# Distortion_outputbuffer.net
KiCad netlist of a schematic drawn in Altium Designer
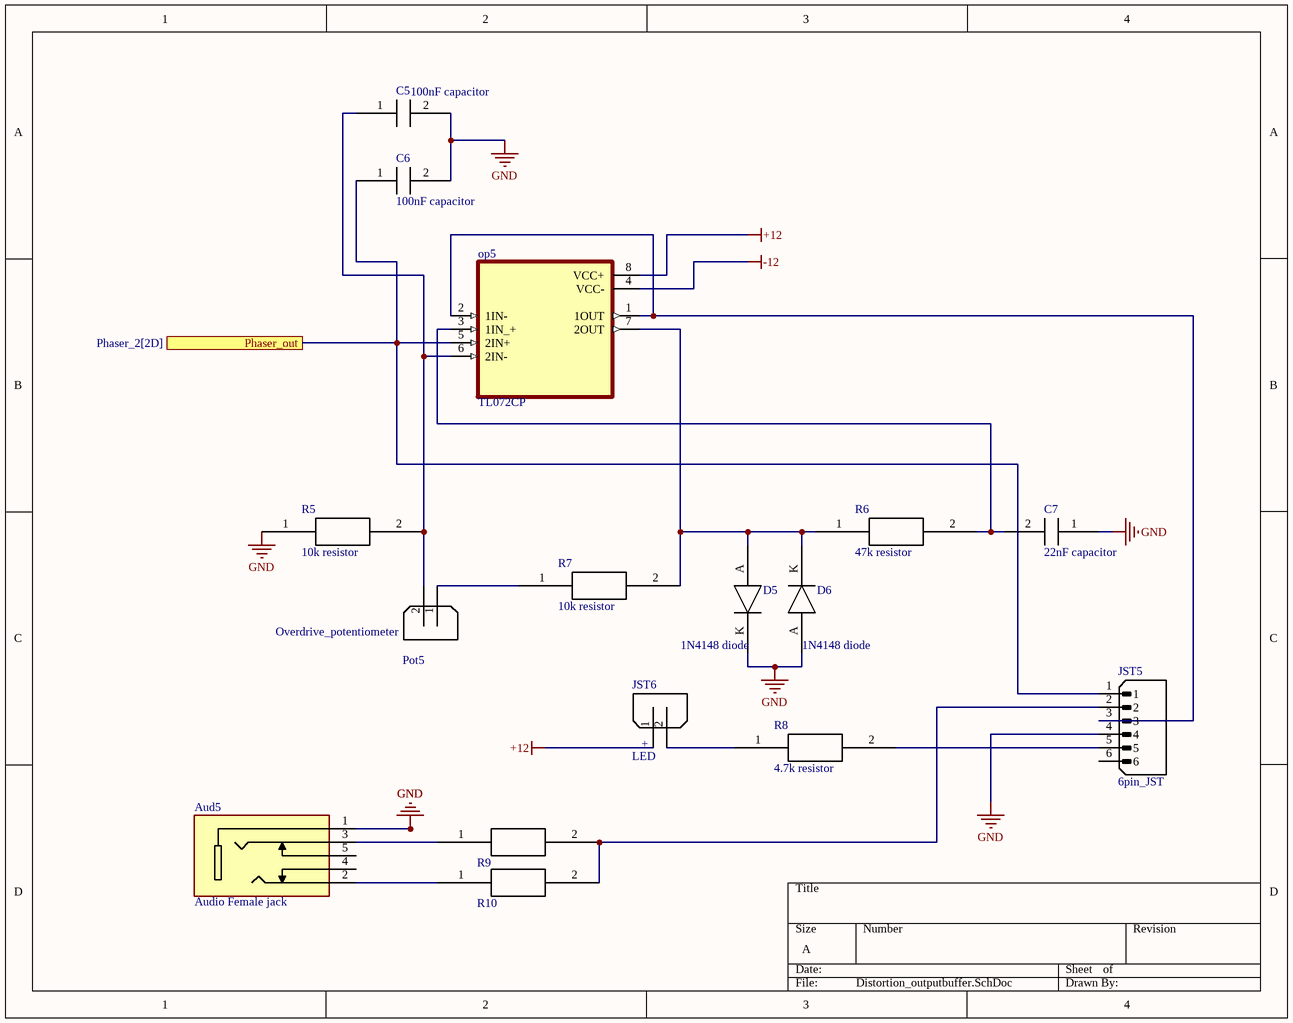
[diagram p0: Distortion_outputbuffer.SchDoc]

(export (version "E")
  (design (tool "Eeschema 10.0.6"))
  (components
    (comp (ref "Aud5")
      (value "Audio Female jack")
      (footprint "Audio Female Jack")
      (libsource (lib "Analog_Project_Schlib") (part "Audio Female jack"))
    )
    (comp (ref "C5")
      (value "100nF capacitor")
      (footprint "100nF")
      (libsource (lib "Analog_Project_Schlib") (part "100nF capacitor"))
    )
    (comp (ref "C6")
      (value "100nF capacitor")
      (footprint "100nF")
      (libsource (lib "Analog_Project_Schlib") (part "100nF capacitor"))
    )
    (comp (ref "C7")
      (value "22nF capacitor")
      (footprint "22nF")
      (libsource (lib "Analog_Project_Schlib") (part "22nF capacitor"))
    )
    (comp (ref "D5")
      (value "1N4148 diode")
      (footprint "1N4148")
      (libsource (lib "Analog_Project_Schlib") (part "1N4148 diode"))
    )
    (comp (ref "D6")
      (value "1N4148 diode")
      (footprint "1N4148")
      (libsource (lib "Analog_Project_Schlib") (part "1N4148 diode"))
    )
    (comp (ref "JST5")
      (value "6pin_JST")
      (footprint "6pin_JST")
      (libsource (lib "Analog_Project_Schlib") (part "6pin_JST"))
    )
    (comp (ref "JST6")
      (value "LED")
      (footprint "2pin_JST")
      (libsource (lib "Analog_Project_Schlib") (part "2pin_JST"))
    )
    (comp (ref "op5")
      (value "TL072CP")
      (footprint "TL072CP")
      (libsource (lib "Analog_Project_Schlib") (part "TL072CP"))
    )
    (comp (ref "Pot5")
      (value "Overdrive_potentiometer")
      (footprint "2pin_JST_non_polarized")
      (libsource (lib "Analog_Project_Schlib") (part "2pin_jst_non_polarized"))
    )
    (comp (ref "R5")
      (value "10k resistor")
      (footprint "10k")
      (libsource (lib "Analog_Project_Schlib") (part "10k resistor"))
    )
    (comp (ref "R6")
      (value "47k resistor")
      (footprint "47k")
      (libsource (lib "Analog_Project_Schlib") (part "47k resistor"))
    )
    (comp (ref "R7")
      (value "10k resistor")
      (footprint "10k")
      (libsource (lib "Analog_Project_Schlib") (part "10k resistor"))
    )
    (comp (ref "R8")
      (value "4.7k resistor")
      (footprint "4.7k")
      (libsource (lib "Analog_Project_Schlib") (part "4.7k resistor"))
    )
    (comp (ref "R9")
      (value "100ohm resistor")
      (footprint "100")
      (libsource (lib "Analog_Project_Schlib") (part "100ohm resistor"))
    )
    (comp (ref "R10")
      (value "100ohm resistor")
      (footprint "100")
      (libsource (lib "Analog_Project_Schlib") (part "100ohm resistor"))
    )
  )
  (nets
    (net (code "1") (name "+12") (class "Default")
      (node (ref "JST6") (pin "1") (pinfunction "1_1") (pintype "passive"))
      (node (ref "op5") (pin "8") (pinfunction "VCC+_8") (pintype "power_in"))
    )
    (net (code "2") (name "-12") (class "Default")
      (node (ref "op5") (pin "4") (pinfunction "VCC-_4") (pintype "power_in"))
    )
    (net (code "3") (name "/Phaser_out") (class "Default")
      (node (ref "C6") (pin "1") (pinfunction "1_1") (pintype "passive"))
      (node (ref "JST5") (pin "1") (pinfunction "1_1") (pintype "passive"))
      (node (ref "op5") (pin "5") (pinfunction "2IN+_5") (pintype "input"))
    )
    (net (code "4") (name "GND") (class "Default")
      (node (ref "Aud5") (pin "1") (pinfunction "1_1") (pintype "passive"))
      (node (ref "C5") (pin "2") (pintype "passive"))
      (node (ref "C6") (pin "2") (pintype "passive"))
      (node (ref "C7") (pin "1") (pinfunction "1_1") (pintype "passive"))
      (node (ref "D5") (pin "K") (pinfunction "K_K") (pintype "passive"))
      (node (ref "D6") (pin "A") (pinfunction "A_A") (pintype "passive"))
      (node (ref "JST5") (pin "4") (pinfunction "4_4") (pintype "passive"))
      (node (ref "R5") (pin "1") (pinfunction "1_1") (pintype "passive"))
    )
    (net (code "5") (name "Net-(Aud5-Pad2)") (class "Default")
      (node (ref "Aud5") (pin "2") (pinfunction "2_2") (pintype "passive"))
      (node (ref "R10") (pin "1") (pinfunction "1_1") (pintype "passive"))
    )
    (net (code "6") (name "Net-(Aud5-Pad3)") (class "Default")
      (node (ref "Aud5") (pin "3") (pinfunction "3_3") (pintype "passive"))
      (node (ref "R9") (pin "1") (pinfunction "1_1") (pintype "passive"))
    )
    (net (code "7") (name "Net-(C7-_2)") (class "Default")
      (node (ref "C7") (pin "2") (pinfunction "_2_2") (pintype "passive"))
      (node (ref "R6") (pin "2") (pinfunction "2_2") (pintype "passive"))
      (node (ref "op5") (pin "3") (pinfunction "1IN_+_3") (pintype "input"))
    )
    (net (code "8") (name "Net-(JST5-Pad2)") (class "Default")
      (node (ref "JST5") (pin "2") (pinfunction "2_2") (pintype "passive"))
      (node (ref "R10") (pin "2") (pinfunction "2_2") (pintype "passive"))
      (node (ref "R9") (pin "2") (pinfunction "2_2") (pintype "passive"))
    )
    (net (code "9") (name "Net-(JST5-Pad5)") (class "Default")
      (node (ref "JST5") (pin "5") (pinfunction "5_5") (pintype "passive"))
      (node (ref "R8") (pin "2") (pinfunction "2_2") (pintype "passive"))
    )
    (net (code "10") (name "Net-(JST6-Pad2)") (class "Default")
      (node (ref "JST6") (pin "2") (pinfunction "2_2") (pintype "passive"))
      (node (ref "R8") (pin "1") (pinfunction "1_1") (pintype "passive"))
    )
    (net (code "11") (name "Net-(Pot5-Pad1)") (class "Default")
      (node (ref "Pot5") (pin "1") (pinfunction "1_1") (pintype "passive"))
      (node (ref "R7") (pin "1") (pinfunction "1_1") (pintype "passive"))
    )
    (net (code "12") (name "Net-(op5-1IN-)") (class "Default")
      (node (ref "JST5") (pin "3") (pinfunction "3_3") (pintype "passive"))
      (node (ref "op5") (pin "1") (pinfunction "1OUT_1") (pintype "output"))
      (node (ref "op5") (pin "2") (pinfunction "1IN-_2") (pintype "input"))
    )
    (net (code "13") (name "Net-(op5-2IN-)") (class "Default")
      (node (ref "C5") (pin "1") (pinfunction "1_1") (pintype "passive"))
      (node (ref "Pot5") (pin "2") (pinfunction "2_2") (pintype "passive"))
      (node (ref "R5") (pin "2") (pinfunction "2_2") (pintype "passive"))
      (node (ref "op5") (pin "6") (pinfunction "2IN-_6") (pintype "input"))
    )
    (net (code "14") (name "Net-(op5-2OUT)") (class "Default")
      (node (ref "D5") (pin "A") (pinfunction "A_A") (pintype "passive"))
      (node (ref "D6") (pin "K") (pinfunction "K_K") (pintype "passive"))
      (node (ref "R6") (pin "1") (pinfunction "1_1") (pintype "passive"))
      (node (ref "R7") (pin "2") (pinfunction "2_2") (pintype "passive"))
      (node (ref "op5") (pin "7") (pinfunction "2OUT_7") (pintype "output"))
    )
    (net (code "15") (name "unconnected-(Aud5-Pad4)") (class "Default")
      (node (ref "Aud5") (pin "4") (pinfunction "4_4") (pintype "passive"))
    )
    (net (code "16") (name "unconnected-(Aud5-Pad5)") (class "Default")
      (node (ref "Aud5") (pin "5") (pinfunction "5_5") (pintype "passive"))
    )
    (net (code "17") (name "unconnected-(JST5-Pad6)") (class "Default")
      (node (ref "JST5") (pin "6") (pinfunction "6_6") (pintype "passive"))
    )
  )
)
